# mcu_rev2.net
KiCad netlist of a schematic drawn in EAGLE
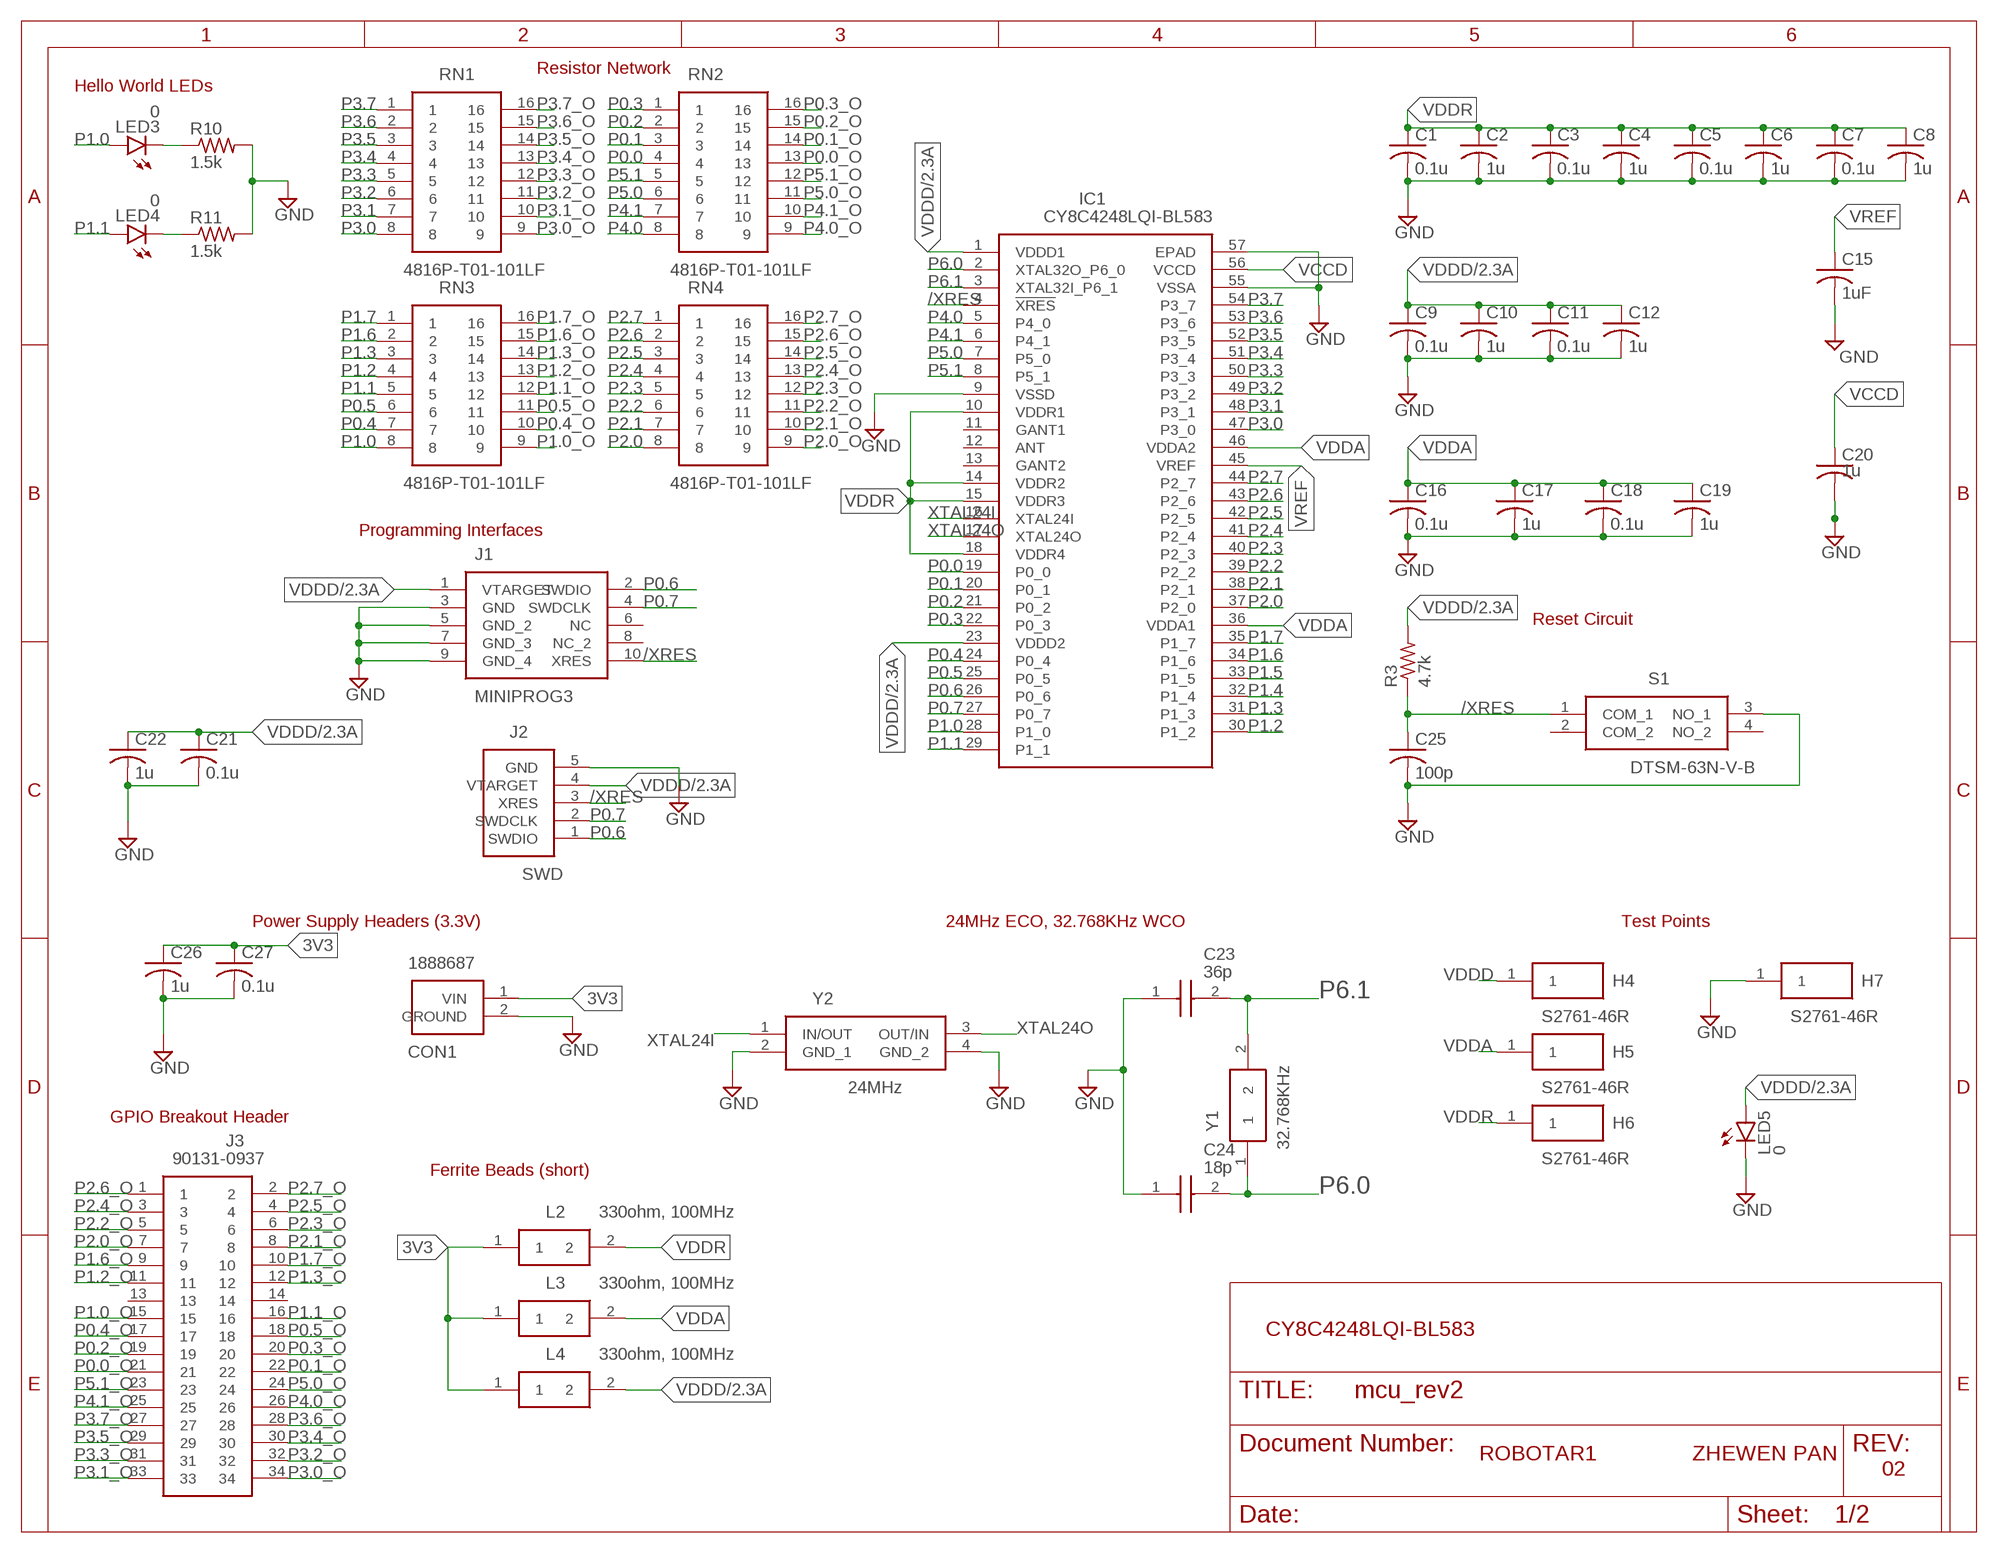
[diagram p0: schematic, sheet 1]
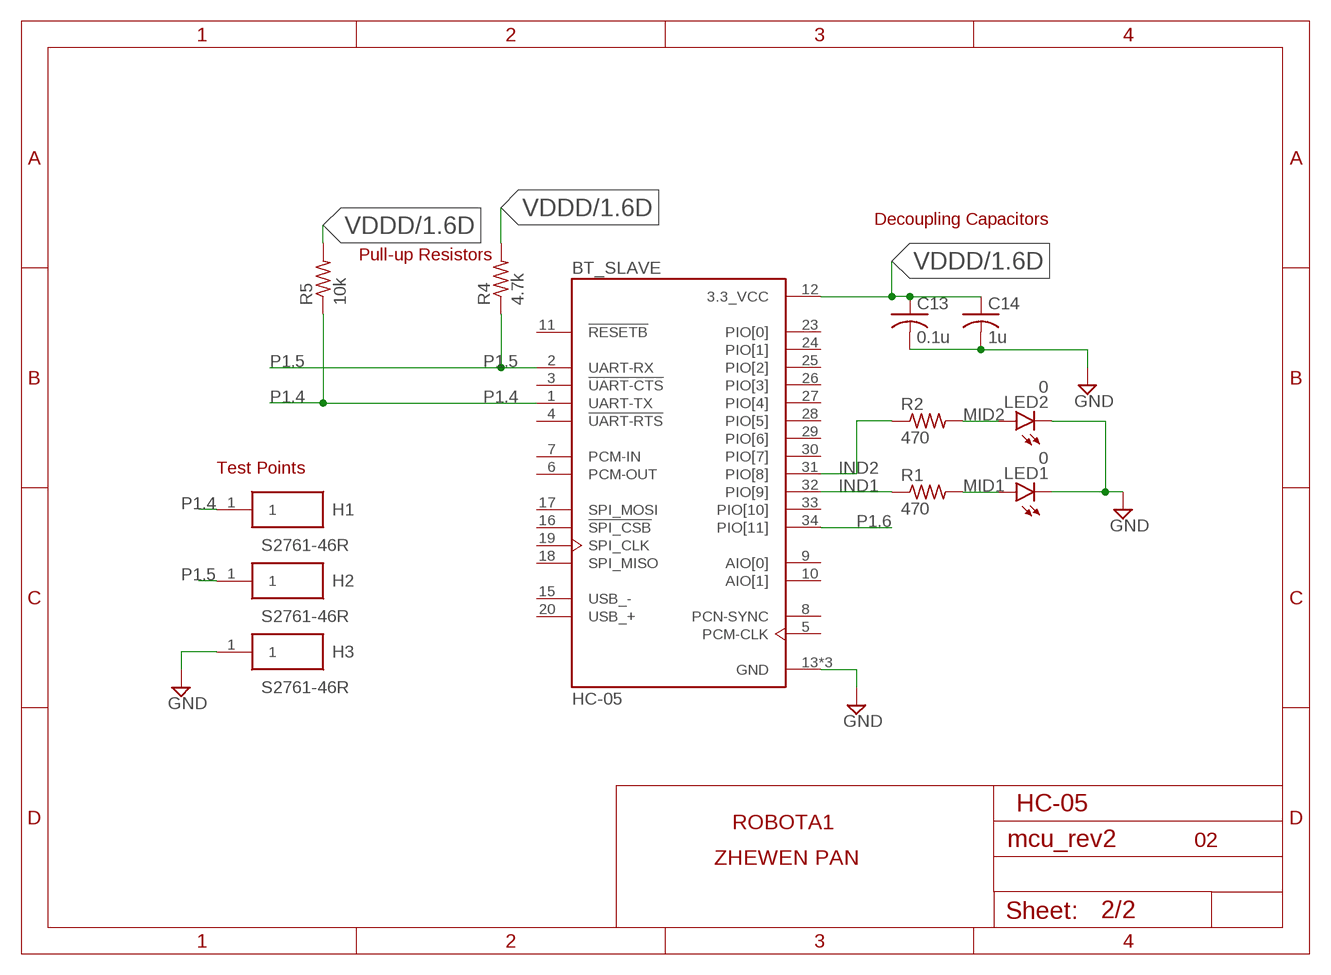
[diagram p1: schematic, sheet 2]

(export (version "E")
  (design (tool "Eeschema 10.0.6"))
  (components
    (comp (ref "C1")
      (value "0.1u")
      (footprint "eagle-import:C0805")
      (libsource (lib "eagle-import") (part "C-USC0805"))
    )
    (comp (ref "C2")
      (value "1u")
      (footprint "eagle-import:C0805")
      (libsource (lib "eagle-import") (part "C-USC0805"))
    )
    (comp (ref "C3")
      (value "0.1u")
      (footprint "eagle-import:C0805")
      (libsource (lib "eagle-import") (part "C-USC0805"))
    )
    (comp (ref "C4")
      (value "1u")
      (footprint "eagle-import:C0805")
      (libsource (lib "eagle-import") (part "C-USC0805"))
    )
    (comp (ref "C5")
      (value "0.1u")
      (footprint "eagle-import:C0805")
      (libsource (lib "eagle-import") (part "C-USC0805"))
    )
    (comp (ref "C6")
      (value "1u")
      (footprint "eagle-import:C0805")
      (libsource (lib "eagle-import") (part "C-USC0805"))
    )
    (comp (ref "C7")
      (value "0.1u")
      (footprint "eagle-import:C0805")
      (libsource (lib "eagle-import") (part "C-USC0805"))
    )
    (comp (ref "C8")
      (value "1u")
      (footprint "eagle-import:C0805")
      (libsource (lib "eagle-import") (part "C-USC0805"))
    )
    (comp (ref "C9")
      (value "0.1u")
      (footprint "eagle-import:C0805")
      (libsource (lib "eagle-import") (part "C-USC0805"))
    )
    (comp (ref "C10")
      (value "1u")
      (footprint "eagle-import:C0805")
      (libsource (lib "eagle-import") (part "C-USC0805"))
    )
    (comp (ref "C11")
      (value "0.1u")
      (footprint "eagle-import:C0805")
      (libsource (lib "eagle-import") (part "C-USC0805"))
    )
    (comp (ref "C12")
      (value "1u")
      (footprint "eagle-import:C0805")
      (libsource (lib "eagle-import") (part "C-USC0805"))
    )
    (comp (ref "C15")
      (value "1uF")
      (footprint "eagle-import:C0805")
      (libsource (lib "eagle-import") (part "C-USC0805"))
    )
    (comp (ref "C16")
      (value "0.1u")
      (footprint "eagle-import:C0805")
      (libsource (lib "eagle-import") (part "C-USC0805"))
    )
    (comp (ref "C17")
      (value "1u")
      (footprint "eagle-import:C0805")
      (libsource (lib "eagle-import") (part "C-USC0805"))
    )
    (comp (ref "C18")
      (value "0.1u")
      (footprint "eagle-import:C0805")
      (libsource (lib "eagle-import") (part "C-USC0805"))
    )
    (comp (ref "C19")
      (value "1u")
      (footprint "eagle-import:C0805")
      (libsource (lib "eagle-import") (part "C-USC0805"))
    )
    (comp (ref "C20")
      (value "1u")
      (footprint "eagle-import:C0805")
      (libsource (lib "eagle-import") (part "C-USC0805"))
    )
    (comp (ref "C21")
      (value "0.1u")
      (footprint "eagle-import:C0805")
      (libsource (lib "eagle-import") (part "C-USC0805"))
    )
    (comp (ref "C22")
      (value "1u")
      (footprint "eagle-import:C0805")
      (libsource (lib "eagle-import") (part "C-USC0805"))
    )
    (comp (ref "C23")
      (value "36p")
      (footprint "eagle-import:CAPC1005X55N")
      (fields
        (field (name "MANUFACTURER_PART_NUMBER") "GRM1555C1H360JA01D")
        (field (name "RS_PART_NUMBER") "8145643P")
      )
      (libsource (lib "eagle-import") (part "GRM1555C1H360JA01D"))
    )
    (comp (ref "C24")
      (value "18p")
      (footprint "eagle-import:CAPC1005X55N")
      (fields
        (field (name "MANUFACTURER_PART_NUMBER") "GRM1555C1H180FA01D")
        (field (name "RS_PART_NUMBER") "7235373P")
      )
      (libsource (lib "eagle-import") (part "GRM1555C1H180FA01D"))
    )
    (comp (ref "C25")
      (value "100p")
      (footprint "eagle-import:C0805")
      (libsource (lib "eagle-import") (part "C-USC0805"))
    )
    (comp (ref "C26")
      (value "1u")
      (footprint "eagle-import:C0805")
      (libsource (lib "eagle-import") (part "C-USC0805"))
    )
    (comp (ref "C27")
      (value "0.1u")
      (footprint "eagle-import:C0805")
      (libsource (lib "eagle-import") (part "C-USC0805"))
    )
    (comp (ref "CON1")
      (value "1888687")
      (footprint "eagle-import:SHDR2W90P0X508_1X2_1016X950X15")
      (fields (field (name "RS_PART_NUMBER") "8045095"))
      (libsource (lib "eagle-import") (part "1888687"))
    )
    (comp (ref "H4")
      (value "S2761-46R")
      (footprint "eagle-import:S276146R")
      (libsource (lib "eagle-import") (part "S2761-46R"))
    )
    (comp (ref "H5")
      (value "S2761-46R")
      (footprint "eagle-import:S276146R")
      (libsource (lib "eagle-import") (part "S2761-46R"))
    )
    (comp (ref "H6")
      (value "S2761-46R")
      (footprint "eagle-import:S276146R")
      (libsource (lib "eagle-import") (part "S2761-46R"))
    )
    (comp (ref "H7")
      (value "S2761-46R")
      (footprint "eagle-import:S276146R")
      (libsource (lib "eagle-import") (part "S2761-46R"))
    )
    (comp (ref "IC1")
      (value "CY8C4248LQI-BL583")
      (footprint "eagle-import:QFN40P700X700X60-57N")
      (fields (field (name "RS_PART_NUMBER") "1771220P"))
      (libsource (lib "eagle-import") (part "CY8C4248LQI-BL583"))
    )
    (comp (ref "J1")
      (value "MINIPROG3")
      (footprint "eagle-import:FTSH-105-01-L-DV-K")
      (fields
        (field (name "MANUFACTURER_PART_NUMBER") "FTSH-105-01-L-DV-K")
        (field (name "RS_PART_NUMBER") "1592332")
      )
      (libsource (lib "eagle-import") (part "FTSH-105-01-L-DV-K"))
    )
    (comp (ref "J2")
      (value "SWD")
      (footprint "eagle-import:HDRV5W64P0X254_1X5_1255X635X81")
      (fields
        (field (name "MANUFACTURER_PART_NUMBER") "22-23-2051")
        (field (name "RS_PART_NUMBER") "1888757")
      )
      (libsource (lib "eagle-import") (part "22-23-2051"))
    )
    (comp (ref "J3")
      (value "90131-0937")
      (footprint "eagle-import:HDRV34W90P254_2X17_4308X500X56")
      (fields (field (name "RS_PART_NUMBER") "6703569"))
      (libsource (lib "eagle-import") (part "90131-0937"))
    )
    (comp (ref "L2")
      (value "330ohm, 100MHz")
      (footprint "eagle-import:BEADC2012X105N")
      (fields
        (field (name "MANUFACTURER_PART_NUMBER") "BLM21PG331SN1D")
        (field (name "RS_PART_NUMBER") "7241545P")
      )
      (libsource (lib "eagle-import") (part "BLM21PG331SN1D"))
    )
    (comp (ref "L3")
      (value "330ohm, 100MHz")
      (footprint "eagle-import:BEADC2012X105N")
      (fields
        (field (name "MANUFACTURER_PART_NUMBER") "BLM21PG331SN1D")
        (field (name "RS_PART_NUMBER") "7241545P")
      )
      (libsource (lib "eagle-import") (part "BLM21PG331SN1D"))
    )
    (comp (ref "L4")
      (value "330ohm, 100MHz")
      (footprint "eagle-import:BEADC2012X105N")
      (fields
        (field (name "MANUFACTURER_PART_NUMBER") "BLM21PG331SN1D")
        (field (name "RS_PART_NUMBER") "7241545P")
      )
      (libsource (lib "eagle-import") (part "BLM21PG331SN1D"))
    )
    (comp (ref "LED3")
      (value "0")
      (footprint "eagle-import:SML0805")
      (libsource (lib "eagle-import") (part "LEDSML0805"))
    )
    (comp (ref "LED4")
      (value "0")
      (footprint "eagle-import:SML0805")
      (libsource (lib "eagle-import") (part "LEDSML0805"))
    )
    (comp (ref "LED5")
      (value "0")
      (footprint "eagle-import:CHIP-LED0805")
      (libsource (lib "eagle-import") (part "LEDCHIP-LED0805"))
    )
    (comp (ref "R3")
      (value "4.7k")
      (footprint "eagle-import:R0805")
      (libsource (lib "eagle-import") (part "R-US_R0805"))
    )
    (comp (ref "R10")
      (value "1.5k")
      (footprint "eagle-import:R0805")
      (libsource (lib "eagle-import") (part "R-US_R0805"))
    )
    (comp (ref "R11")
      (value "1.5k")
      (footprint "eagle-import:R0805")
      (libsource (lib "eagle-import") (part "R-US_R0805"))
    )
    (comp (ref "RN1")
      (value "4816P-T01-101LF")
      (footprint "eagle-import:SOIC127P762X215-16N")
      (fields (field (name "RS_PART_NUMBER") "5224942P"))
      (libsource (lib "eagle-import") (part "4816P-T01-101LF"))
    )
    (comp (ref "RN2")
      (value "4816P-T01-101LF")
      (footprint "eagle-import:SOIC127P762X215-16N")
      (fields (field (name "RS_PART_NUMBER") "5224942P"))
      (libsource (lib "eagle-import") (part "4816P-T01-101LF"))
    )
    (comp (ref "RN3")
      (value "4816P-T01-101LF")
      (footprint "eagle-import:SOIC127P762X215-16N")
      (fields (field (name "RS_PART_NUMBER") "5224942P"))
      (libsource (lib "eagle-import") (part "4816P-T01-101LF"))
    )
    (comp (ref "RN4")
      (value "4816P-T01-101LF")
      (footprint "eagle-import:SOIC127P762X215-16N")
      (fields (field (name "RS_PART_NUMBER") "5224942P"))
      (libsource (lib "eagle-import") (part "4816P-T01-101LF"))
    )
    (comp (ref "S1")
      (value "DTSM-63N-V-B")
      (footprint "eagle-import:DTSM63NVB")
      (libsource (lib "eagle-import") (part "DTSM-63N-V-B"))
    )
    (comp (ref "Y1")
      (value "32.768KHz")
      (footprint "eagle-import:ECX-31B")
      (fields (field (name "MANUFACTURER_PART_NUMBER") "ECS-.327-12.5-34B-TR"))
      (libsource (lib "eagle-import") (part "ECS-.327-12.5-34B-TR"))
    )
    (comp (ref "Y2")
      (value "24MHz")
      (footprint "eagle-import:ECS240836QAESTR")
      (fields (field (name "MANUFACTURER_PART_NUMBER") "ECS-240-8-36CKM-TR") (field (name "SPICEPREFIX") "E"))
      (libsource (lib "eagle-import") (part "ECS-240-8-36CKM-TR"))
    )
    (comp (ref "BT_SLAVE")
      (value "HC-05")
      (footprint "eagle-import:XCVR_HC-05")
      (fields (field (name "MF") "Texas Instruments") (field (name "SPICEPREFIX") "X"))
      (libsource (lib "eagle-import") (part "HC-05"))
    )
    (comp (ref "C13")
      (value "0.1u")
      (footprint "eagle-import:C0805")
      (libsource (lib "eagle-import") (part "C-USC0805"))
    )
    (comp (ref "C14")
      (value "1u")
      (footprint "eagle-import:C0805")
      (libsource (lib "eagle-import") (part "C-USC0805"))
    )
    (comp (ref "H1")
      (value "S2761-46R")
      (footprint "eagle-import:S276146R")
      (libsource (lib "eagle-import") (part "S2761-46R"))
    )
    (comp (ref "H2")
      (value "S2761-46R")
      (footprint "eagle-import:S276146R")
      (libsource (lib "eagle-import") (part "S2761-46R"))
    )
    (comp (ref "H3")
      (value "S2761-46R")
      (footprint "eagle-import:S276146R")
      (libsource (lib "eagle-import") (part "S2761-46R"))
    )
    (comp (ref "LED1")
      (value "0")
      (footprint "eagle-import:SML0805")
      (libsource (lib "eagle-import") (part "LEDSML0805"))
    )
    (comp (ref "LED2")
      (value "0")
      (footprint "eagle-import:SML0805")
      (libsource (lib "eagle-import") (part "LEDSML0805"))
    )
    (comp (ref "R1")
      (value "470")
      (footprint "eagle-import:R0805")
      (libsource (lib "eagle-import") (part "R-US_R0805"))
    )
    (comp (ref "R2")
      (value "470")
      (footprint "eagle-import:R0805")
      (libsource (lib "eagle-import") (part "R-US_R0805"))
    )
    (comp (ref "R4")
      (value "4.7k")
      (footprint "eagle-import:R0805")
      (libsource (lib "eagle-import") (part "R-US_R0805"))
    )
    (comp (ref "R5")
      (value "10k")
      (footprint "eagle-import:R0805")
      (libsource (lib "eagle-import") (part "R-US_R0805"))
    )
  )
  (nets
    (net (code "1") (name "3V3") (class "Default")
      (node (ref "C26") (pin "1") (pinfunction "1_1") (pintype "passive"))
      (node (ref "C27") (pin "1") (pinfunction "1_1") (pintype "passive"))
      (node (ref "CON1") (pin "1") (pinfunction "VIN_1") (pintype "bidirectional"))
      (node (ref "L2") (pin "1") (pinfunction "1_1") (pintype "bidirectional"))
      (node (ref "L3") (pin "1") (pinfunction "1_1") (pintype "bidirectional"))
      (node (ref "L4") (pin "1") (pinfunction "1_1") (pintype "bidirectional"))
    )
    (net (code "2") (name "GND") (class "Default")
      (node (ref "BT_SLAVE") (pin "13") (pinfunction "GND_13") (pintype "power_in"))
      (node (ref "BT_SLAVE") (pin "21") (pinfunction "GND_21") (pintype "power_in"))
      (node (ref "BT_SLAVE") (pin "22") (pinfunction "GND_22") (pintype "power_in"))
      (node (ref "C1") (pin "2") (pinfunction "2_2") (pintype "passive"))
      (node (ref "C10") (pin "2") (pinfunction "2_2") (pintype "passive"))
      (node (ref "C11") (pin "2") (pinfunction "2_2") (pintype "passive"))
      (node (ref "C12") (pin "2") (pinfunction "2_2") (pintype "passive"))
      (node (ref "C13") (pin "2") (pinfunction "2_2") (pintype "passive"))
      (node (ref "C14") (pin "2") (pinfunction "2_2") (pintype "passive"))
      (node (ref "C15") (pin "2") (pinfunction "2_2") (pintype "passive"))
      (node (ref "C16") (pin "2") (pinfunction "2_2") (pintype "passive"))
      (node (ref "C17") (pin "2") (pinfunction "2_2") (pintype "passive"))
      (node (ref "C18") (pin "2") (pinfunction "2_2") (pintype "passive"))
      (node (ref "C19") (pin "2") (pinfunction "2_2") (pintype "passive"))
      (node (ref "C2") (pin "2") (pinfunction "2_2") (pintype "passive"))
      (node (ref "C20") (pin "2") (pinfunction "2_2") (pintype "passive"))
      (node (ref "C21") (pin "2") (pinfunction "2_2") (pintype "passive"))
      (node (ref "C22") (pin "2") (pinfunction "2_2") (pintype "passive"))
      (node (ref "C23") (pin "1") (pinfunction "1_1") (pintype "bidirectional"))
      (node (ref "C24") (pin "1") (pinfunction "1_1") (pintype "bidirectional"))
      (node (ref "C25") (pin "2") (pinfunction "2_2") (pintype "passive"))
      (node (ref "C26") (pin "2") (pinfunction "2_2") (pintype "passive"))
      (node (ref "C27") (pin "2") (pinfunction "2_2") (pintype "passive"))
      (node (ref "C3") (pin "2") (pinfunction "2_2") (pintype "passive"))
      (node (ref "C4") (pin "2") (pinfunction "2_2") (pintype "passive"))
      (node (ref "C5") (pin "2") (pinfunction "2_2") (pintype "passive"))
      (node (ref "C6") (pin "2") (pinfunction "2_2") (pintype "passive"))
      (node (ref "C7") (pin "2") (pinfunction "2_2") (pintype "passive"))
      (node (ref "C8") (pin "2") (pinfunction "2_2") (pintype "passive"))
      (node (ref "C9") (pin "2") (pinfunction "2_2") (pintype "passive"))
      (node (ref "CON1") (pin "2") (pinfunction "GROUND_2") (pintype "bidirectional"))
      (node (ref "H3") (pin "1") (pinfunction "1_1") (pintype "bidirectional"))
      (node (ref "H7") (pin "1") (pinfunction "1_1") (pintype "bidirectional"))
      (node (ref "IC1") (pin "55") (pinfunction "VSSA_55") (pintype "bidirectional"))
      (node (ref "IC1") (pin "57") (pinfunction "EPAD_57") (pintype "bidirectional"))
      (node (ref "IC1") (pin "9") (pinfunction "VSSD_9") (pintype "bidirectional"))
      (node (ref "J1") (pin "3") (pinfunction "GND_3") (pintype "bidirectional"))
      (node (ref "J1") (pin "5") (pinfunction "GND_2_5") (pintype "bidirectional"))
      (node (ref "J1") (pin "7") (pinfunction "GND_3_7") (pintype "bidirectional"))
      (node (ref "J1") (pin "9") (pinfunction "GND_4_9") (pintype "bidirectional"))
      (node (ref "J2") (pin "5") (pinfunction "GND_5") (pintype "bidirectional"))
      (node (ref "LED1") (pin "C") (pinfunction "C_C") (pintype "passive"))
      (node (ref "LED2") (pin "C") (pinfunction "C_C") (pintype "passive"))
      (node (ref "LED5") (pin "C") (pinfunction "C_C") (pintype "passive"))
      (node (ref "R10") (pin "2") (pinfunction "2_2") (pintype "passive"))
      (node (ref "R11") (pin "2") (pinfunction "2_2") (pintype "passive"))
      (node (ref "S1") (pin "3") (pinfunction "NO_1_3") (pintype "bidirectional"))
      (node (ref "Y2") (pin "2") (pinfunction "GND_1_2") (pintype "bidirectional"))
      (node (ref "Y2") (pin "4") (pinfunction "GND_2_4") (pintype "bidirectional"))
    )
    (net (code "3") (name "IND1") (class "Default")
      (node (ref "BT_SLAVE") (pin "32") (pinfunction "PIO[9]_32") (pintype "bidirectional"))
      (node (ref "R1") (pin "1") (pinfunction "1_1") (pintype "passive"))
    )
    (net (code "4") (name "IND2") (class "Default")
      (node (ref "BT_SLAVE") (pin "31") (pinfunction "PIO[8]_31") (pintype "bidirectional"))
      (node (ref "R2") (pin "1") (pinfunction "1_1") (pintype "passive"))
    )
    (net (code "5") (name "MID1") (class "Default")
      (node (ref "LED1") (pin "A") (pinfunction "A_A") (pintype "passive"))
      (node (ref "R1") (pin "2") (pinfunction "2_2") (pintype "passive"))
    )
    (net (code "6") (name "MID2") (class "Default")
      (node (ref "LED2") (pin "A") (pinfunction "A_A") (pintype "passive"))
      (node (ref "R2") (pin "2") (pinfunction "2_2") (pintype "passive"))
    )
    (net (code "7") (name "Net-(LED3-PadC)") (class "Default")
      (node (ref "LED3") (pin "C") (pinfunction "C_C") (pintype "passive"))
      (node (ref "R10") (pin "1") (pinfunction "1_1") (pintype "passive"))
    )
    (net (code "8") (name "Net-(LED4-PadC)") (class "Default")
      (node (ref "LED4") (pin "C") (pinfunction "C_C") (pintype "passive"))
      (node (ref "R11") (pin "1") (pinfunction "1_1") (pintype "passive"))
    )
    (net (code "9") (name "P0.0") (class "Default")
      (node (ref "IC1") (pin "19") (pinfunction "P0_0_19") (pintype "bidirectional"))
      (node (ref "RN2") (pin "4") (pinfunction "4_4") (pintype "bidirectional"))
    )
    (net (code "10") (name "P0.0_O") (class "Default")
      (node (ref "J3") (pin "21") (pinfunction "21_21") (pintype "bidirectional"))
      (node (ref "RN2") (pin "13") (pinfunction "13_13") (pintype "bidirectional"))
    )
    (net (code "11") (name "P0.1") (class "Default")
      (node (ref "IC1") (pin "20") (pinfunction "P0_1_20") (pintype "bidirectional"))
      (node (ref "RN2") (pin "3") (pinfunction "3_3") (pintype "bidirectional"))
    )
    (net (code "12") (name "P0.1_O") (class "Default")
      (node (ref "J3") (pin "22") (pinfunction "22_22") (pintype "bidirectional"))
      (node (ref "RN2") (pin "14") (pinfunction "14_14") (pintype "bidirectional"))
    )
    (net (code "13") (name "P0.2") (class "Default")
      (node (ref "IC1") (pin "21") (pinfunction "P0_2_21") (pintype "bidirectional"))
      (node (ref "RN2") (pin "2") (pinfunction "2_2") (pintype "bidirectional"))
    )
    (net (code "14") (name "P0.2_O") (class "Default")
      (node (ref "J3") (pin "19") (pinfunction "19_19") (pintype "bidirectional"))
      (node (ref "RN2") (pin "15") (pinfunction "15_15") (pintype "bidirectional"))
    )
    (net (code "15") (name "P0.3") (class "Default")
      (node (ref "IC1") (pin "22") (pinfunction "P0_3_22") (pintype "bidirectional"))
      (node (ref "RN2") (pin "1") (pinfunction "1_1") (pintype "bidirectional"))
    )
    (net (code "16") (name "P0.3_O") (class "Default")
      (node (ref "J3") (pin "20") (pinfunction "20_20") (pintype "bidirectional"))
      (node (ref "RN2") (pin "16") (pinfunction "16_16") (pintype "bidirectional"))
    )
    (net (code "17") (name "P0.4") (class "Default")
      (node (ref "IC1") (pin "24") (pinfunction "P0_4_24") (pintype "bidirectional"))
      (node (ref "RN3") (pin "7") (pinfunction "7_7") (pintype "bidirectional"))
    )
    (net (code "18") (name "P0.4_O") (class "Default")
      (node (ref "J3") (pin "17") (pinfunction "17_17") (pintype "bidirectional"))
      (node (ref "RN3") (pin "10") (pinfunction "10_10") (pintype "bidirectional"))
    )
    (net (code "19") (name "P0.5") (class "Default")
      (node (ref "IC1") (pin "25") (pinfunction "P0_5_25") (pintype "bidirectional"))
      (node (ref "RN3") (pin "6") (pinfunction "6_6") (pintype "bidirectional"))
    )
    (net (code "20") (name "P0.5_O") (class "Default")
      (node (ref "J3") (pin "18") (pinfunction "18_18") (pintype "bidirectional"))
      (node (ref "RN3") (pin "11") (pinfunction "11_11") (pintype "bidirectional"))
    )
    (net (code "21") (name "P0.6") (class "Default")
      (node (ref "IC1") (pin "26") (pinfunction "P0_6_26") (pintype "bidirectional"))
      (node (ref "J1") (pin "2") (pinfunction "SWDIO_2") (pintype "bidirectional"))
      (node (ref "J2") (pin "1") (pinfunction "SWDIO_1") (pintype "bidirectional"))
    )
    (net (code "22") (name "P0.7") (class "Default")
      (node (ref "IC1") (pin "27") (pinfunction "P0_7_27") (pintype "bidirectional"))
      (node (ref "J1") (pin "4") (pinfunction "SWDCLK_4") (pintype "bidirectional"))
      (node (ref "J2") (pin "2") (pinfunction "SWDCLK_2") (pintype "bidirectional"))
    )
    (net (code "23") (name "P1.0") (class "Default")
      (node (ref "IC1") (pin "28") (pinfunction "P1_0_28") (pintype "bidirectional"))
      (node (ref "LED3") (pin "A") (pinfunction "A_A") (pintype "passive"))
      (node (ref "RN3") (pin "8") (pinfunction "8_8") (pintype "bidirectional"))
    )
    (net (code "24") (name "P1.0_O") (class "Default")
      (node (ref "J3") (pin "15") (pinfunction "15_15") (pintype "bidirectional"))
      (node (ref "RN3") (pin "9") (pinfunction "9_9") (pintype "bidirectional"))
    )
    (net (code "25") (name "P1.1") (class "Default")
      (node (ref "IC1") (pin "29") (pinfunction "P1_1_29") (pintype "bidirectional"))
      (node (ref "LED4") (pin "A") (pinfunction "A_A") (pintype "passive"))
      (node (ref "RN3") (pin "5") (pinfunction "5_5") (pintype "bidirectional"))
    )
    (net (code "26") (name "P1.1_O") (class "Default")
      (node (ref "J3") (pin "16") (pinfunction "16_16") (pintype "bidirectional"))
      (node (ref "RN3") (pin "12") (pinfunction "12_12") (pintype "bidirectional"))
    )
    (net (code "27") (name "P1.2") (class "Default")
      (node (ref "IC1") (pin "30") (pinfunction "P1_2_30") (pintype "bidirectional"))
      (node (ref "RN3") (pin "4") (pinfunction "4_4") (pintype "bidirectional"))
    )
    (net (code "28") (name "P1.2_O") (class "Default")
      (node (ref "J3") (pin "11") (pinfunction "11_11") (pintype "bidirectional"))
      (node (ref "RN3") (pin "13") (pinfunction "13_13") (pintype "bidirectional"))
    )
    (net (code "29") (name "P1.3") (class "Default")
      (node (ref "IC1") (pin "31") (pinfunction "P1_3_31") (pintype "bidirectional"))
      (node (ref "RN3") (pin "3") (pinfunction "3_3") (pintype "bidirectional"))
    )
    (net (code "30") (name "P1.3_O") (class "Default")
      (node (ref "J3") (pin "12") (pinfunction "12_12") (pintype "bidirectional"))
      (node (ref "RN3") (pin "14") (pinfunction "14_14") (pintype "bidirectional"))
    )
    (net (code "31") (name "P1.4") (class "Default")
      (node (ref "BT_SLAVE") (pin "1") (pinfunction "UART-TX_1") (pintype "output"))
      (node (ref "H1") (pin "1") (pinfunction "1_1") (pintype "bidirectional"))
      (node (ref "IC1") (pin "32") (pinfunction "P1_4_32") (pintype "bidirectional"))
      (node (ref "R5") (pin "1") (pinfunction "1_1") (pintype "passive"))
    )
    (net (code "32") (name "P1.5") (class "Default")
      (node (ref "BT_SLAVE") (pin "2") (pinfunction "UART-RX_2") (pintype "input"))
      (node (ref "H2") (pin "1") (pinfunction "1_1") (pintype "bidirectional"))
      (node (ref "IC1") (pin "33") (pinfunction "P1_5_33") (pintype "bidirectional"))
      (node (ref "R4") (pin "1") (pinfunction "1_1") (pintype "passive"))
    )
    (net (code "33") (name "P1.6") (class "Default")
      (node (ref "BT_SLAVE") (pin "34") (pinfunction "PIO[11]_34") (pintype "bidirectional"))
      (node (ref "IC1") (pin "34") (pinfunction "P1_6_34") (pintype "bidirectional"))
      (node (ref "RN3") (pin "2") (pinfunction "2_2") (pintype "bidirectional"))
    )
    (net (code "34") (name "P1.6_O") (class "Default")
      (node (ref "J3") (pin "9") (pinfunction "9_9") (pintype "bidirectional"))
      (node (ref "RN3") (pin "15") (pinfunction "15_15") (pintype "bidirectional"))
    )
    (net (code "35") (name "P1.7") (class "Default")
      (node (ref "IC1") (pin "35") (pinfunction "P1_7_35") (pintype "bidirectional"))
      (node (ref "RN3") (pin "1") (pinfunction "1_1") (pintype "bidirectional"))
    )
    (net (code "36") (name "P1.7_O") (class "Default")
      (node (ref "J3") (pin "10") (pinfunction "10_10") (pintype "bidirectional"))
      (node (ref "RN3") (pin "16") (pinfunction "16_16") (pintype "bidirectional"))
    )
    (net (code "37") (name "P2.0") (class "Default")
      (node (ref "IC1") (pin "37") (pinfunction "P2_0_37") (pintype "bidirectional"))
      (node (ref "RN4") (pin "8") (pinfunction "8_8") (pintype "bidirectional"))
    )
    (net (code "38") (name "P2.0_O") (class "Default")
      (node (ref "J3") (pin "7") (pinfunction "7_7") (pintype "bidirectional"))
      (node (ref "RN4") (pin "9") (pinfunction "9_9") (pintype "bidirectional"))
    )
    (net (code "39") (name "P2.1") (class "Default")
      (node (ref "IC1") (pin "38") (pinfunction "P2_1_38") (pintype "bidirectional"))
      (node (ref "RN4") (pin "7") (pinfunction "7_7") (pintype "bidirectional"))
    )
    (net (code "40") (name "P2.1_O") (class "Default")
      (node (ref "J3") (pin "8") (pinfunction "8_8") (pintype "bidirectional"))
      (node (ref "RN4") (pin "10") (pinfunction "10_10") (pintype "bidirectional"))
    )
    (net (code "41") (name "P2.2") (class "Default")
      (node (ref "IC1") (pin "39") (pinfunction "P2_2_39") (pintype "bidirectional"))
      (node (ref "RN4") (pin "6") (pinfunction "6_6") (pintype "bidirectional"))
    )
    (net (code "42") (name "P2.2_O") (class "Default")
      (node (ref "J3") (pin "5") (pinfunction "5_5") (pintype "bidirectional"))
      (node (ref "RN4") (pin "11") (pinfunction "11_11") (pintype "bidirectional"))
    )
    (net (code "43") (name "P2.3") (class "Default")
      (node (ref "IC1") (pin "40") (pinfunction "P2_3_40") (pintype "bidirectional"))
      (node (ref "RN4") (pin "5") (pinfunction "5_5") (pintype "bidirectional"))
    )
    (net (code "44") (name "P2.3_O") (class "Default")
      (node (ref "J3") (pin "6") (pinfunction "6_6") (pintype "bidirectional"))
      (node (ref "RN4") (pin "12") (pinfunction "12_12") (pintype "bidirectional"))
    )
    (net (code "45") (name "P2.4") (class "Default")
      (node (ref "IC1") (pin "41") (pinfunction "P2_4_41") (pintype "bidirectional"))
      (node (ref "RN4") (pin "4") (pinfunction "4_4") (pintype "bidirectional"))
    )
    (net (code "46") (name "P2.4_O") (class "Default")
      (node (ref "J3") (pin "3") (pinfunction "3_3") (pintype "bidirectional"))
      (node (ref "RN4") (pin "13") (pinfunction "13_13") (pintype "bidirectional"))
    )
    (net (code "47") (name "P2.5") (class "Default")
      (node (ref "IC1") (pin "42") (pinfunction "P2_5_42") (pintype "bidirectional"))
      (node (ref "RN4") (pin "3") (pinfunction "3_3") (pintype "bidirectional"))
    )
    (net (code "48") (name "P2.5_O") (class "Default")
      (node (ref "J3") (pin "4") (pinfunction "4_4") (pintype "bidirectional"))
      (node (ref "RN4") (pin "14") (pinfunction "14_14") (pintype "bidirectional"))
    )
    (net (code "49") (name "P2.6") (class "Default")
      (node (ref "IC1") (pin "43") (pinfunction "P2_6_43") (pintype "bidirectional"))
      (node (ref "RN4") (pin "2") (pinfunction "2_2") (pintype "bidirectional"))
    )
    (net (code "50") (name "P2.6_O") (class "Default")
      (node (ref "J3") (pin "1") (pinfunction "1_1") (pintype "bidirectional"))
      (node (ref "RN4") (pin "15") (pinfunction "15_15") (pintype "bidirectional"))
    )
    (net (code "51") (name "P2.7") (class "Default")
      (node (ref "IC1") (pin "44") (pinfunction "P2_7_44") (pintype "bidirectional"))
      (node (ref "RN4") (pin "1") (pinfunction "1_1") (pintype "bidirectional"))
    )
    (net (code "52") (name "P2.7_O") (class "Default")
      (node (ref "J3") (pin "2") (pinfunction "2_2") (pintype "bidirectional"))
      (node (ref "RN4") (pin "16") (pinfunction "16_16") (pintype "bidirectional"))
    )
    (net (code "53") (name "P3.0") (class "Default")
      (node (ref "IC1") (pin "47") (pinfunction "P3_0_47") (pintype "bidirectional"))
      (node (ref "RN1") (pin "8") (pinfunction "8_8") (pintype "bidirectional"))
    )
    (net (code "54") (name "P3.0_O") (class "Default")
      (node (ref "J3") (pin "34") (pinfunction "34_34") (pintype "bidirectional"))
      (node (ref "RN1") (pin "9") (pinfunction "9_9") (pintype "bidirectional"))
    )
    (net (code "55") (name "P3.1") (class "Default")
      (node (ref "IC1") (pin "48") (pinfunction "P3_1_48") (pintype "bidirectional"))
      (node (ref "RN1") (pin "7") (pinfunction "7_7") (pintype "bidirectional"))
    )
    (net (code "56") (name "P3.1_O") (class "Default")
      (node (ref "J3") (pin "33") (pinfunction "33_33") (pintype "bidirectional"))
      (node (ref "RN1") (pin "10") (pinfunction "10_10") (pintype "bidirectional"))
    )
    (net (code "57") (name "P3.2") (class "Default")
      (node (ref "IC1") (pin "49") (pinfunction "P3_2_49") (pintype "bidirectional"))
      (node (ref "RN1") (pin "6") (pinfunction "6_6") (pintype "bidirectional"))
    )
    (net (code "58") (name "P3.2_O") (class "Default")
      (node (ref "J3") (pin "32") (pinfunction "32_32") (pintype "bidirectional"))
      (node (ref "RN1") (pin "11") (pinfunction "11_11") (pintype "bidirectional"))
    )
    (net (code "59") (name "P3.3") (class "Default")
      (node (ref "IC1") (pin "50") (pinfunction "P3_3_50") (pintype "bidirectional"))
      (node (ref "RN1") (pin "5") (pinfunction "5_5") (pintype "bidirectional"))
    )
    (net (code "60") (name "P3.3_O") (class "Default")
      (node (ref "J3") (pin "31") (pinfunction "31_31") (pintype "bidirectional"))
      (node (ref "RN1") (pin "12") (pinfunction "12_12") (pintype "bidirectional"))
    )
    (net (code "61") (name "P3.4") (class "Default")
      (node (ref "IC1") (pin "51") (pinfunction "P3_4_51") (pintype "bidirectional"))
      (node (ref "RN1") (pin "4") (pinfunction "4_4") (pintype "bidirectional"))
    )
    (net (code "62") (name "P3.4_O") (class "Default")
      (node (ref "J3") (pin "30") (pinfunction "30_30") (pintype "bidirectional"))
      (node (ref "RN1") (pin "13") (pinfunction "13_13") (pintype "bidirectional"))
    )
    (net (code "63") (name "P3.5") (class "Default")
      (node (ref "IC1") (pin "52") (pinfunction "P3_5_52") (pintype "bidirectional"))
      (node (ref "RN1") (pin "3") (pinfunction "3_3") (pintype "bidirectional"))
    )
    (net (code "64") (name "P3.5_O") (class "Default")
      (node (ref "J3") (pin "29") (pinfunction "29_29") (pintype "bidirectional"))
      (node (ref "RN1") (pin "14") (pinfunction "14_14") (pintype "bidirectional"))
    )
    (net (code "65") (name "P3.6") (class "Default")
      (node (ref "IC1") (pin "53") (pinfunction "P3_6_53") (pintype "bidirectional"))
      (node (ref "RN1") (pin "2") (pinfunction "2_2") (pintype "bidirectional"))
    )
    (net (code "66") (name "P3.6_O") (class "Default")
      (node (ref "J3") (pin "28") (pinfunction "28_28") (pintype "bidirectional"))
      (node (ref "RN1") (pin "15") (pinfunction "15_15") (pintype "bidirectional"))
    )
    (net (code "67") (name "P3.7") (class "Default")
      (node (ref "IC1") (pin "54") (pinfunction "P3_7_54") (pintype "bidirectional"))
      (node (ref "RN1") (pin "1") (pinfunction "1_1") (pintype "bidirectional"))
    )
    (net (code "68") (name "P3.7_O") (class "Default")
      (node (ref "J3") (pin "27") (pinfunction "27_27") (pintype "bidirectional"))
      (node (ref "RN1") (pin "16") (pinfunction "16_16") (pintype "bidirectional"))
    )
    (net (code "69") (name "P4.0") (class "Default")
      (node (ref "IC1") (pin "5") (pinfunction "P4_0_5") (pintype "bidirectional"))
      (node (ref "RN2") (pin "8") (pinfunction "8_8") (pintype "bidirectional"))
    )
    (net (code "70") (name "P4.0_O") (class "Default")
      (node (ref "J3") (pin "26") (pinfunction "26_26") (pintype "bidirectional"))
      (node (ref "RN2") (pin "9") (pinfunction "9_9") (pintype "bidirectional"))
    )
    (net (code "71") (name "P4.1") (class "Default")
      (node (ref "IC1") (pin "6") (pinfunction "P4_1_6") (pintype "bidirectional"))
      (node (ref "RN2") (pin "7") (pinfunction "7_7") (pintype "bidirectional"))
    )
    (net (code "72") (name "P4.1_O") (class "Default")
      (node (ref "J3") (pin "25") (pinfunction "25_25") (pintype "bidirectional"))
      (node (ref "RN2") (pin "10") (pinfunction "10_10") (pintype "bidirectional"))
    )
    (net (code "73") (name "P5.0") (class "Default")
      (node (ref "IC1") (pin "7") (pinfunction "P5_0_7") (pintype "bidirectional"))
      (node (ref "RN2") (pin "6") (pinfunction "6_6") (pintype "bidirectional"))
    )
    (net (code "74") (name "P5.0_O") (class "Default")
      (node (ref "J3") (pin "24") (pinfunction "24_24") (pintype "bidirectional"))
      (node (ref "RN2") (pin "11") (pinfunction "11_11") (pintype "bidirectional"))
    )
    (net (code "75") (name "P5.1") (class "Default")
      (node (ref "IC1") (pin "8") (pinfunction "P5_1_8") (pintype "bidirectional"))
      (node (ref "RN2") (pin "5") (pinfunction "5_5") (pintype "bidirectional"))
    )
    (net (code "76") (name "P5.1_O") (class "Default")
      (node (ref "J3") (pin "23") (pinfunction "23_23") (pintype "bidirectional"))
      (node (ref "RN2") (pin "12") (pinfunction "12_12") (pintype "bidirectional"))
    )
    (net (code "77") (name "P6.0") (class "Default")
      (node (ref "C24") (pin "2") (pinfunction "2_2") (pintype "bidirectional"))
      (node (ref "IC1") (pin "2") (pinfunction "XTAL32O_P6_0_2") (pintype "bidirectional"))
      (node (ref "Y1") (pin "1") (pinfunction "1_1") (pintype "bidirectional"))
    )
    (net (code "78") (name "P6.1") (class "Default")
      (node (ref "C23") (pin "2") (pinfunction "2_2") (pintype "bidirectional"))
      (node (ref "IC1") (pin "3") (pinfunction "XTAL32I_P6_1_3") (pintype "bidirectional"))
      (node (ref "Y1") (pin "2") (pinfunction "2_2") (pintype "bidirectional"))
    )
    (net (code "79") (name "VCCD") (class "Default")
      (node (ref "C20") (pin "1") (pinfunction "1_1") (pintype "passive"))
      (node (ref "IC1") (pin "56") (pinfunction "VCCD_56") (pintype "bidirectional"))
    )
    (net (code "80") (name "VDDA") (class "Default")
      (node (ref "C16") (pin "1") (pinfunction "1_1") (pintype "passive"))
      (node (ref "C17") (pin "1") (pinfunction "1_1") (pintype "passive"))
      (node (ref "C18") (pin "1") (pinfunction "1_1") (pintype "passive"))
      (node (ref "C19") (pin "1") (pinfunction "1_1") (pintype "passive"))
      (node (ref "H5") (pin "1") (pinfunction "1_1") (pintype "bidirectional"))
      (node (ref "IC1") (pin "36") (pinfunction "VDDA1_36") (pintype "bidirectional"))
      (node (ref "IC1") (pin "46") (pinfunction "VDDA2_46") (pintype "bidirectional"))
      (node (ref "L3") (pin "2") (pinfunction "2_2") (pintype "bidirectional"))
    )
    (net (code "81") (name "VDDD") (class "Default")
      (node (ref "BT_SLAVE") (pin "12") (pinfunction "3.3_VCC_12") (pintype "power_in"))
      (node (ref "C10") (pin "1") (pinfunction "1_1") (pintype "passive"))
      (node (ref "C11") (pin "1") (pinfunction "1_1") (pintype "passive"))
      (node (ref "C12") (pin "1") (pinfunction "1_1") (pintype "passive"))
      (node (ref "C13") (pin "1") (pinfunction "1_1") (pintype "passive"))
      (node (ref "C14") (pin "1") (pinfunction "1_1") (pintype "passive"))
      (node (ref "C21") (pin "1") (pinfunction "1_1") (pintype "passive"))
      (node (ref "C22") (pin "1") (pinfunction "1_1") (pintype "passive"))
      (node (ref "C9") (pin "1") (pinfunction "1_1") (pintype "passive"))
      (node (ref "H4") (pin "1") (pinfunction "1_1") (pintype "bidirectional"))
      (node (ref "IC1") (pin "1") (pinfunction "VDDD1_1") (pintype "bidirectional"))
      (node (ref "IC1") (pin "23") (pinfunction "VDDD2_23") (pintype "bidirectional"))
      (node (ref "J1") (pin "1") (pinfunction "VTARGET_1") (pintype "bidirectional"))
      (node (ref "J2") (pin "4") (pinfunction "VTARGET_4") (pintype "bidirectional"))
      (node (ref "L4") (pin "2") (pinfunction "2_2") (pintype "bidirectional"))
      (node (ref "LED5") (pin "A") (pinfunction "A_A") (pintype "passive"))
      (node (ref "R3") (pin "2") (pinfunction "2_2") (pintype "passive"))
      (node (ref "R4") (pin "2") (pinfunction "2_2") (pintype "passive"))
      (node (ref "R5") (pin "2") (pinfunction "2_2") (pintype "passive"))
    )
    (net (code "82") (name "VDDR") (class "Default")
      (node (ref "C1") (pin "1") (pinfunction "1_1") (pintype "passive"))
      (node (ref "C2") (pin "1") (pinfunction "1_1") (pintype "passive"))
      (node (ref "C3") (pin "1") (pinfunction "1_1") (pintype "passive"))
      (node (ref "C4") (pin "1") (pinfunction "1_1") (pintype "passive"))
      (node (ref "C5") (pin "1") (pinfunction "1_1") (pintype "passive"))
      (node (ref "C6") (pin "1") (pinfunction "1_1") (pintype "passive"))
      (node (ref "C7") (pin "1") (pinfunction "1_1") (pintype "passive"))
      (node (ref "C8") (pin "1") (pinfunction "1_1") (pintype "passive"))
      (node (ref "H6") (pin "1") (pinfunction "1_1") (pintype "bidirectional"))
      (node (ref "IC1") (pin "10") (pinfunction "VDDR1_10") (pintype "bidirectional"))
      (node (ref "IC1") (pin "14") (pinfunction "VDDR2_14") (pintype "bidirectional"))
      (node (ref "IC1") (pin "15") (pinfunction "VDDR3_15") (pintype "bidirectional"))
      (node (ref "IC1") (pin "18") (pinfunction "VDDR4_18") (pintype "bidirectional"))
      (node (ref "L2") (pin "2") (pinfunction "2_2") (pintype "bidirectional"))
    )
    (net (code "83") (name "VREF") (class "Default")
      (node (ref "C15") (pin "1") (pinfunction "1_1") (pintype "passive"))
      (node (ref "IC1") (pin "45") (pinfunction "VREF_45") (pintype "bidirectional"))
    )
    (net (code "84") (name "XTAL24I") (class "Default")
      (node (ref "IC1") (pin "16") (pinfunction "XTAL24I_16") (pintype "bidirectional"))
      (node (ref "Y2") (pin "1") (pinfunction "IN/OUT_1") (pintype "bidirectional"))
    )
    (net (code "85") (name "XTAL24O") (class "Default")
      (node (ref "IC1") (pin "17") (pinfunction "XTAL24O_17") (pintype "bidirectional"))
      (node (ref "Y2") (pin "3") (pinfunction "OUT/IN_3") (pintype "bidirectional"))
    )
    (net (code "86") (name "unconnected-(BT_SLAVE-AIO[0]-Pad9)") (class "Default")
      (node (ref "BT_SLAVE") (pin "9") (pinfunction "AIO[0]_9") (pintype "bidirectional"))
    )
    (net (code "87") (name "unconnected-(BT_SLAVE-AIO[1]-Pad10)") (class "Default")
      (node (ref "BT_SLAVE") (pin "10") (pinfunction "AIO[1]_10") (pintype "bidirectional"))
    )
    (net (code "88") (name "unconnected-(BT_SLAVE-PCM-CLK-Pad5)") (class "Default")
      (node (ref "BT_SLAVE") (pin "5") (pinfunction "PCM-CLK_5") (pintype "bidirectional"))
    )
    (net (code "89") (name "unconnected-(BT_SLAVE-PCM-IN-Pad7)") (class "Default")
      (node (ref "BT_SLAVE") (pin "7") (pinfunction "PCM-IN_7") (pintype "input"))
    )
    (net (code "90") (name "unconnected-(BT_SLAVE-PCM-OUT-Pad6)") (class "Default")
      (node (ref "BT_SLAVE") (pin "6") (pinfunction "PCM-OUT_6") (pintype "output"))
    )
    (net (code "91") (name "unconnected-(BT_SLAVE-PCN-SYNC-Pad8)") (class "Default")
      (node (ref "BT_SLAVE") (pin "8") (pinfunction "PCN-SYNC_8") (pintype "bidirectional"))
    )
    (net (code "92") (name "unconnected-(BT_SLAVE-PIO[0]-Pad23)") (class "Default")
      (node (ref "BT_SLAVE") (pin "23") (pinfunction "PIO[0]_23") (pintype "bidirectional"))
    )
    (net (code "93") (name "unconnected-(BT_SLAVE-PIO[1]-Pad24)") (class "Default")
      (node (ref "BT_SLAVE") (pin "24") (pinfunction "PIO[1]_24") (pintype "bidirectional"))
    )
    (net (code "94") (name "unconnected-(BT_SLAVE-PIO[2]-Pad25)") (class "Default")
      (node (ref "BT_SLAVE") (pin "25") (pinfunction "PIO[2]_25") (pintype "bidirectional"))
    )
    (net (code "95") (name "unconnected-(BT_SLAVE-PIO[3]-Pad26)") (class "Default")
      (node (ref "BT_SLAVE") (pin "26") (pinfunction "PIO[3]_26") (pintype "bidirectional"))
    )
    (net (code "96") (name "unconnected-(BT_SLAVE-PIO[4]-Pad27)") (class "Default")
      (node (ref "BT_SLAVE") (pin "27") (pinfunction "PIO[4]_27") (pintype "bidirectional"))
    )
    (net (code "97") (name "unconnected-(BT_SLAVE-PIO[5]-Pad28)") (class "Default")
      (node (ref "BT_SLAVE") (pin "28") (pinfunction "PIO[5]_28") (pintype "bidirectional"))
    )
    (net (code "98") (name "unconnected-(BT_SLAVE-PIO[6]-Pad29)") (class "Default")
      (node (ref "BT_SLAVE") (pin "29") (pinfunction "PIO[6]_29") (pintype "bidirectional"))
    )
    (net (code "99") (name "unconnected-(BT_SLAVE-PIO[7]-Pad30)") (class "Default")
      (node (ref "BT_SLAVE") (pin "30") (pinfunction "PIO[7]_30") (pintype "bidirectional"))
    )
    (net (code "100") (name "unconnected-(BT_SLAVE-PIO[10]-Pad33)") (class "Default")
      (node (ref "BT_SLAVE") (pin "33") (pinfunction "PIO[10]_33") (pintype "bidirectional"))
    )
    (net (code "101") (name "unconnected-(BT_SLAVE-SPI_CLK-Pad19)") (class "Default")
      (node (ref "BT_SLAVE") (pin "19") (pinfunction "SPI_CLK_19") (pintype "input"))
    )
    (net (code "102") (name "unconnected-(BT_SLAVE-SPI_MISO-Pad18)") (class "Default")
      (node (ref "BT_SLAVE") (pin "18") (pinfunction "SPI_MISO_18") (pintype "output"))
    )
    (net (code "103") (name "unconnected-(BT_SLAVE-SPI_MOSI-Pad17)") (class "Default")
      (node (ref "BT_SLAVE") (pin "17") (pinfunction "SPI_MOSI_17") (pintype "input"))
    )
    (net (code "104") (name "unconnected-(BT_SLAVE-USB_+-Pad20)") (class "Default")
      (node (ref "BT_SLAVE") (pin "20") (pinfunction "USB_+_20") (pintype "bidirectional"))
    )
    (net (code "105") (name "unconnected-(BT_SLAVE-USB_--Pad15)") (class "Default")
      (node (ref "BT_SLAVE") (pin "15") (pinfunction "USB_-_15") (pintype "bidirectional"))
    )
    (net (code "106") (name "unconnected-(BT_SLAVE-~{RESETB}-Pad11)") (class "Default")
      (node (ref "BT_SLAVE") (pin "11") (pinfunction "~{RESETB}_11") (pintype "input"))
    )
    (net (code "107") (name "unconnected-(BT_SLAVE-~{SPI_CSB}-Pad16)") (class "Default")
      (node (ref "BT_SLAVE") (pin "16") (pinfunction "~{SPI_CSB}_16") (pintype "input"))
    )
    (net (code "108") (name "unconnected-(BT_SLAVE-~{UART-CTS}-Pad3)") (class "Default")
      (node (ref "BT_SLAVE") (pin "3") (pinfunction "~{UART-CTS}_3") (pintype "input"))
    )
    (net (code "109") (name "unconnected-(BT_SLAVE-~{UART-RTS}-Pad4)") (class "Default")
      (node (ref "BT_SLAVE") (pin "4") (pinfunction "~{UART-RTS}_4") (pintype "output"))
    )
    (net (code "110") (name "unconnected-(IC1-ANT-Pad12)") (class "Default")
      (node (ref "IC1") (pin "12") (pinfunction "ANT_12") (pintype "bidirectional"))
    )
    (net (code "111") (name "unconnected-(IC1-GANT1-Pad11)") (class "Default")
      (node (ref "IC1") (pin "11") (pinfunction "GANT1_11") (pintype "bidirectional"))
    )
    (net (code "112") (name "unconnected-(IC1-GANT2-Pad13)") (class "Default")
      (node (ref "IC1") (pin "13") (pinfunction "GANT2_13") (pintype "bidirectional"))
    )
    (net (code "113") (name "unconnected-(J1-NC-Pad6)") (class "Default")
      (node (ref "J1") (pin "6") (pinfunction "NC_6") (pintype "bidirectional"))
    )
    (net (code "114") (name "unconnected-(J1-NC_2-Pad8)") (class "Default")
      (node (ref "J1") (pin "8") (pinfunction "NC_2_8") (pintype "bidirectional"))
    )
    (net (code "115") (name "unconnected-(J3-Pad13)") (class "Default")
      (node (ref "J3") (pin "13") (pinfunction "13_13") (pintype "bidirectional"))
    )
    (net (code "116") (name "unconnected-(J3-Pad14)") (class "Default")
      (node (ref "J3") (pin "14") (pinfunction "14_14") (pintype "bidirectional"))
    )
    (net (code "117") (name "unconnected-(S1-COM_2-Pad2)") (class "Default")
      (node (ref "S1") (pin "2") (pinfunction "COM_2_2") (pintype "bidirectional"))
    )
    (net (code "118") (name "unconnected-(S1-NO_2-Pad4)") (class "Default")
      (node (ref "S1") (pin "4") (pinfunction "NO_2_4") (pintype "bidirectional"))
    )
    (net (code "119") (name "{slash}XRES") (class "Default")
      (node (ref "C25") (pin "1") (pinfunction "1_1") (pintype "passive"))
      (node (ref "IC1") (pin "4") (pinfunction "~{XRES}_4") (pintype "bidirectional"))
      (node (ref "J1") (pin "10") (pinfunction "XRES_10") (pintype "bidirectional"))
      (node (ref "J2") (pin "3") (pinfunction "XRES_3") (pintype "bidirectional"))
      (node (ref "R3") (pin "1") (pinfunction "1_1") (pintype "passive"))
      (node (ref "S1") (pin "1") (pinfunction "COM_1_1") (pintype "bidirectional"))
    )
  )
)
